# 32x35_V0_6.net
KiCad netlist of a schematic drawn in Altium Designer
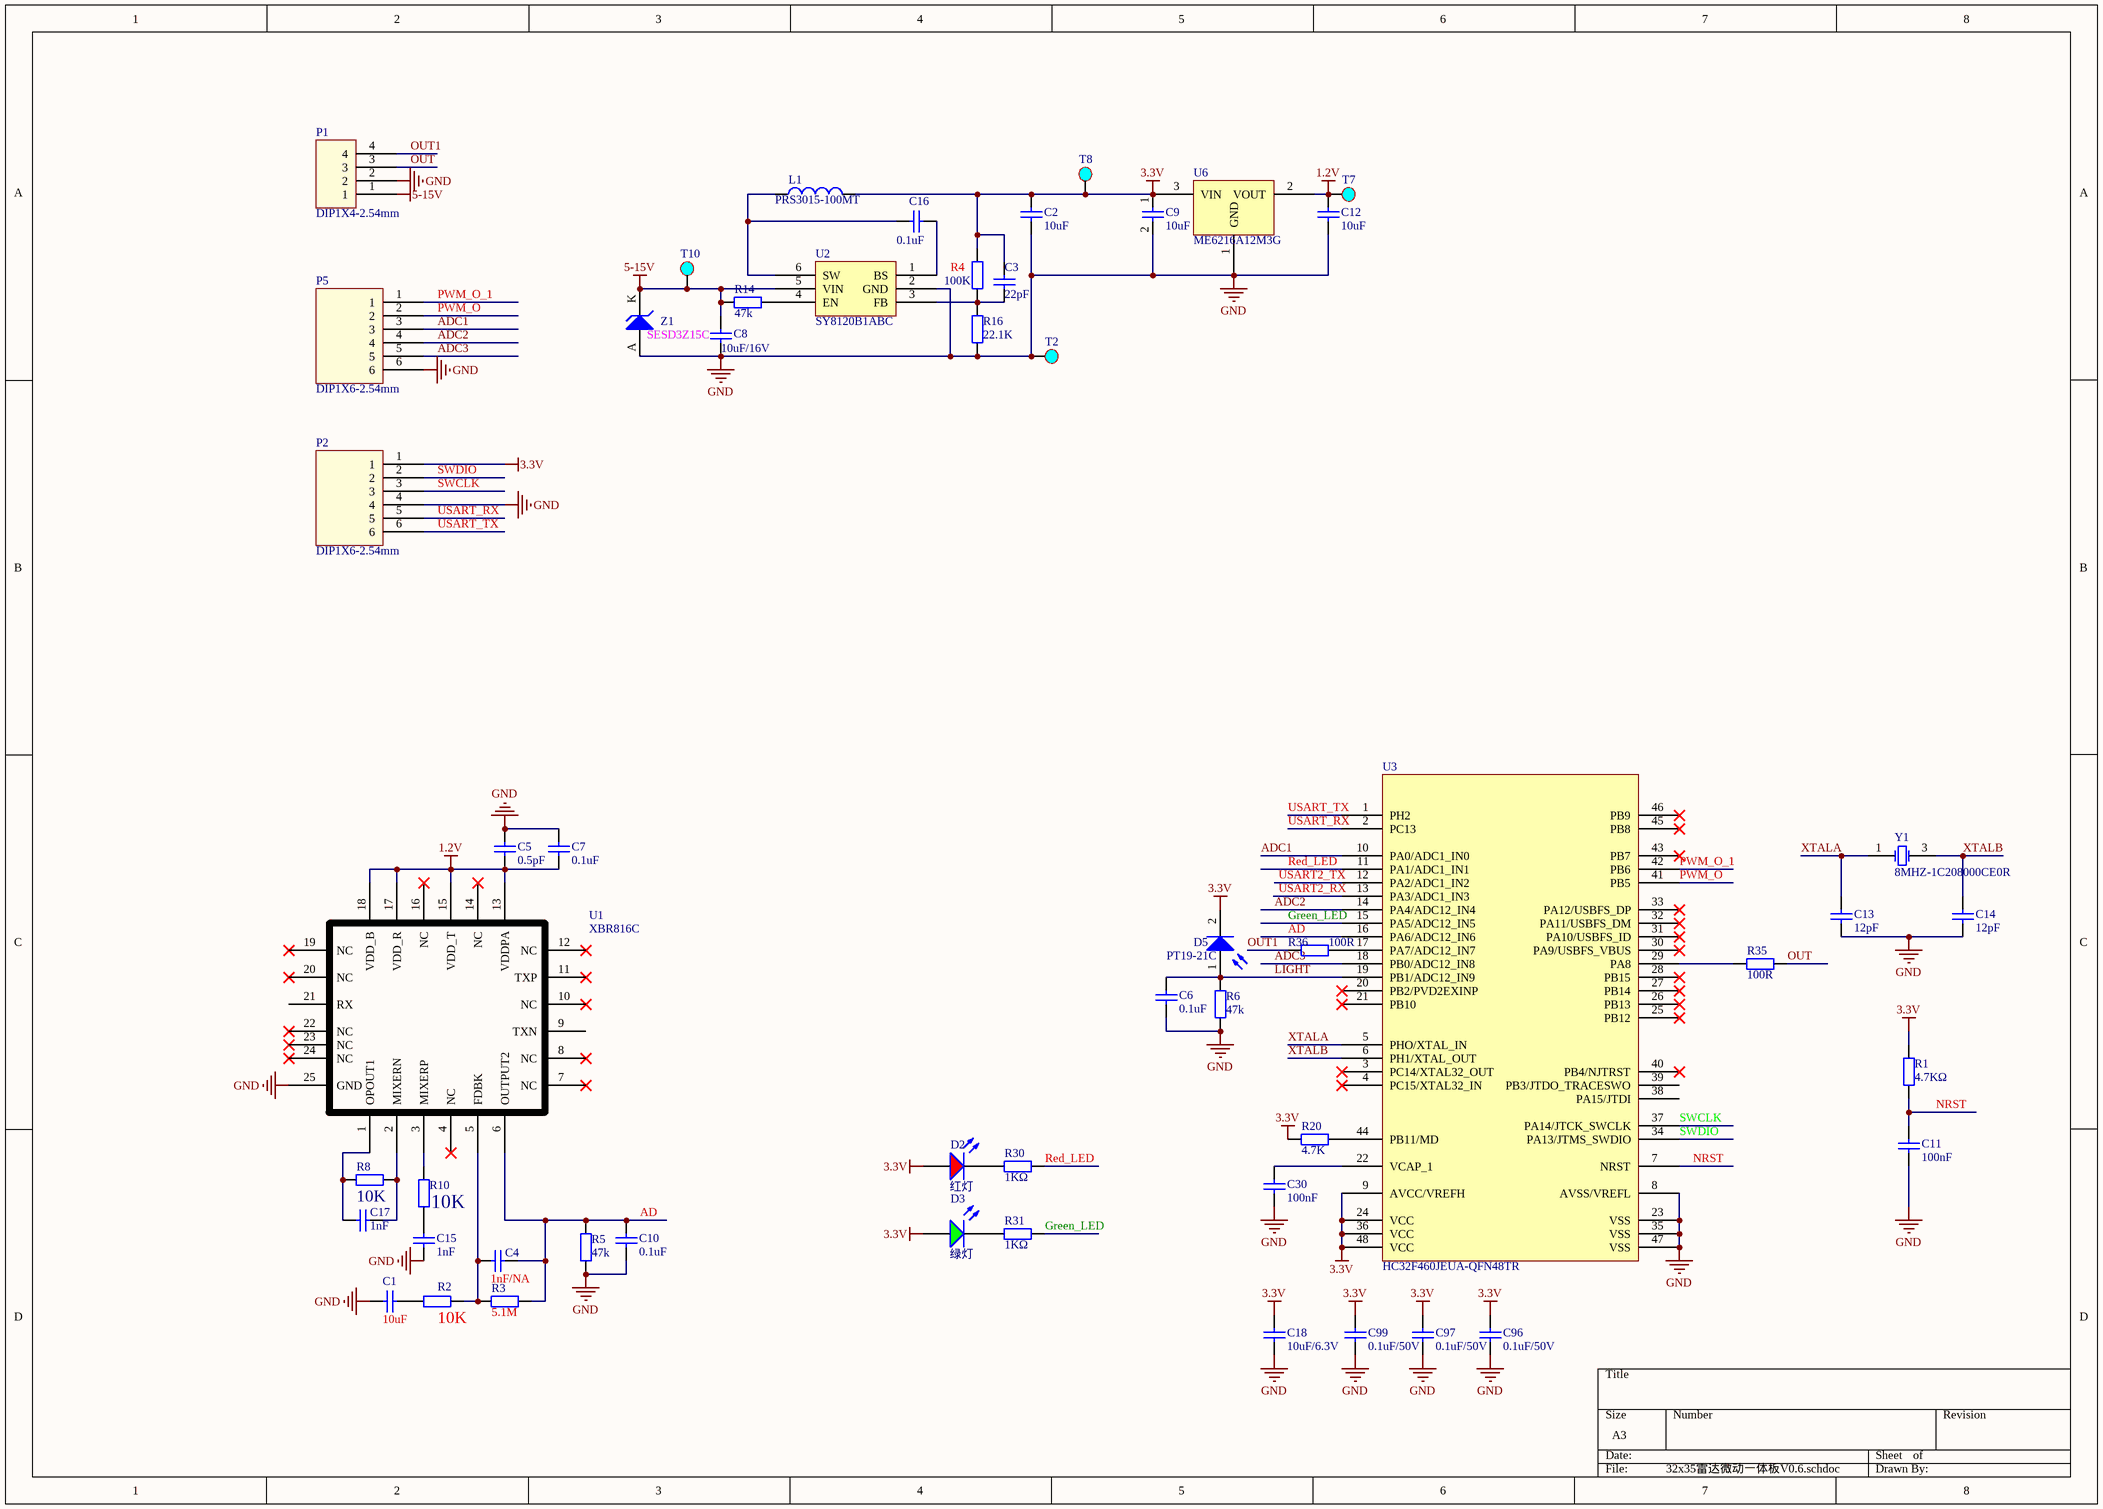
[diagram p0: 32x35雷达微动一体板V0.6.schdoc]

(export (version "E")
  (design (tool "Eeschema 10.0.6"))
  (components
    (comp (ref "C1")
      (value "10uF")
      (footprint "C0402")
      (description "Capacitor")
      (fields (field (name "PUBLISHER") "Altium Limited"))
      (libsource (lib "Miscellaneous Devices") (part "Cap"))
    )
    (comp (ref "C2")
      (value "10uF")
      (footprint "C0402")
      (description "Capacitor")
      (fields (field (name "PUBLISHER") "Altium Limited"))
      (libsource (lib "Miscellaneous Devices") (part "Cap"))
    )
    (comp (ref "C3")
      (value "22pF")
      (footprint "C0402")
      (description "Capacitor")
      (fields (field (name "PUBLISHER") "Altium Limited"))
      (libsource (lib "Miscellaneous Devices") (part "Cap"))
    )
    (comp (ref "C4")
      (value "1nF/NA")
      (footprint "C0402")
      (description "Capacitor")
      (fields (field (name "PUBLISHER") "Altium Limited"))
      (libsource (lib "Miscellaneous Devices") (part "Cap"))
    )
    (comp (ref "C5")
      (value "0.5pF")
      (footprint "C0402")
      (description "Capacitor")
      (fields (field (name "PUBLISHER") "Altium Limited"))
      (libsource (lib "Miscellaneous Devices") (part "Cap"))
    )
    (comp (ref "C6")
      (value "0.1uF")
      (footprint "C0402")
      (description "Capacitor")
      (fields (field (name "PUBLISHER") "Altium Limited"))
      (libsource (lib "Miscellaneous Devices") (part "Cap"))
    )
    (comp (ref "C7")
      (value "0.1uF")
      (footprint "C0402")
      (description "Capacitor")
      (fields (field (name "PUBLISHER") "Altium Limited"))
      (libsource (lib "Miscellaneous Devices") (part "Cap"))
    )
    (comp (ref "C8")
      (value "10uF/16V")
      (footprint "C0603")
      (description "Capacitor")
      (fields (field (name "PUBLISHER") "Altium Limited"))
      (libsource (lib "Miscellaneous Devices") (part "Cap"))
    )
    (comp (ref "C9")
      (value "10uF")
      (footprint "C0402")
      (description "Capacitor")
      (fields (field (name "PUBLISHER") "Altium Limited"))
      (libsource (lib "") (part "Cap_1"))
    )
    (comp (ref "C10")
      (value "0.1uF")
      (footprint "C0402")
      (description "Capacitor")
      (fields (field (name "PUBLISHER") "Altium Limited"))
      (libsource (lib "Miscellaneous Devices") (part "Cap"))
    )
    (comp (ref "C11")
      (value "100nF")
      (footprint "C0402")
      (description "贴片电容")
      (libsource (lib "Miscellaneous Devices LC") (part "0402 100nF (104) 10% 16V"))
    )
    (comp (ref "C12")
      (value "10uF")
      (footprint "C0402")
      (description "Capacitor")
      (fields (field (name "PUBLISHER") "Altium Limited"))
      (libsource (lib "Miscellaneous Devices") (part "Cap"))
    )
    (comp (ref "C13")
      (value "12pF")
      (footprint "C0402")
      (description "贴片电容")
      (libsource (lib "Cap") (part "0402 22pF (220) 5% 50V"))
    )
    (comp (ref "C14")
      (value "12pF")
      (footprint "C0402")
      (description "贴片电容")
      (libsource (lib "Cap") (part "0402 22pF (220) 5% 50V"))
    )
    (comp (ref "C15")
      (value "1nF")
      (footprint "C0402")
      (description "Capacitor")
      (fields (field (name "PUBLISHER") "Altium Limited"))
      (libsource (lib "Miscellaneous Devices") (part "Cap"))
    )
    (comp (ref "C16")
      (value "0.1uF")
      (footprint "C0402")
      (description "Capacitor")
      (fields (field (name "PUBLISHER") "Altium Limited"))
      (libsource (lib "Miscellaneous Devices") (part "Cap"))
    )
    (comp (ref "C17")
      (value "1nF")
      (footprint "C0402")
      (description "Capacitor")
      (fields (field (name "PUBLISHER") "Altium Limited"))
      (libsource (lib "Miscellaneous Devices") (part "Cap"))
    )
    (comp (ref "C18")
      (value "10uF/6.3V")
      (footprint "C0402")
      (description "贴片电容")
      (libsource (lib "Cap") (part "0402 2.2nF (222) 10% 50V"))
    )
    (comp (ref "C30")
      (value "100nF")
      (footprint "C0402")
      (description "Capacitor")
      (fields (field (name "PUBLISHER") "Altium Limited"))
      (libsource (lib "Miscellaneous Devices") (part "Cap"))
    )
    (comp (ref "C96")
      (value "0.1uF/50V")
      (footprint "C0402")
      (description "贴片电容")
      (libsource (lib "Cap") (part "0402 2.2nF (222) 10% 50V"))
    )
    (comp (ref "C97")
      (value "0.1uF/50V")
      (footprint "C0402")
      (description "贴片电容")
      (libsource (lib "Cap") (part "0402 2.2nF (222) 10% 50V"))
    )
    (comp (ref "C99")
      (value "0.1uF/50V")
      (footprint "C0402")
      (description "贴片电容")
      (libsource (lib "Cap") (part "0402 2.2nF (222) 10% 50V"))
    )
    (comp (ref "D2")
      (value "红灯")
      (footprint "LC-0603_LED_S1")
      (description "发光二极管")
      (libsource (lib "Miscellaneous Devices LC") (part "0603 红灯"))
    )
    (comp (ref "D3")
      (value "绿灯")
      (footprint "LC-0603_LED_S1")
      (description "发光二极管")
      (libsource (lib "30x35雷达微动底板V0.2") (part "0603 红灯"))
    )
    (comp (ref "D5")
      (value "PT19-21C")
      (footprint "LED-0603")
      (description "Photosensitive Diode")
      (fields (field (name "PUBLISHER") "Altium Limited"))
      (libsource (lib "Miscellaneous Devices") (part "Photo Sen"))
    )
    (comp (ref "L1")
      (value "PRS3015-100MT")
      (footprint "PRS3015")
      (description "Inductor")
      (fields (field (name "PUBLISHER") "Altium Limited"))
      (libsource (lib "Miscellaneous Devices") (part "Inductor"))
    )
    (comp (ref "P1")
      (value "DIP1X4-2.54mm")
      (footprint "DIP1X4-2.54mm")
      (libsource (lib "30x35雷达微动底板V0.2") (part "DIP4-2.54mm"))
    )
    (comp (ref "P2")
      (value "DIP1X6-2.54mm")
      (footprint "DIP1X6-2.54")
      (libsource (lib "30x35雷达微动底板V0.2") (part "DIP1X6-2.54mm"))
    )
    (comp (ref "P5")
      (value "DIP1X6-2.54mm")
      (footprint "DIP1X6-2.54")
      (libsource (lib "30x35雷达微动底板V0.2") (part "DIP1X6-2.54mm"))
    )
    (comp (ref "R1")
      (value "4.7KΩ")
      (footprint "R0402")
      (description "贴片电阻")
      (libsource (lib "") (part "0402 4.7KΩ (4701) 1%_1"))
    )
    (comp (ref "R2")
      (value "10K")
      (footprint "R0402")
      (description "Resistor")
      (fields (field (name "PUBLISHER") "Altium Limited"))
      (libsource (lib "") (part "Res2_1"))
    )
    (comp (ref "R3")
      (value "5.1M")
      (footprint "R0402")
      (description "Resistor")
      (fields (field (name "PUBLISHER") "Altium Limited"))
      (libsource (lib "Miscellaneous Devices") (part "Res2"))
    )
    (comp (ref "R4")
      (value "100K")
      (footprint "R0402")
      (description "Resistor")
      (fields (field (name "PUBLISHER") "Altium Limited"))
      (libsource (lib "") (part "Res2_3"))
    )
    (comp (ref "R5")
      (value "47k")
      (footprint "R0402")
      (description "Resistor")
      (fields (field (name "PUBLISHER") "Altium Limited"))
      (libsource (lib "") (part "Res2_2"))
    )
    (comp (ref "R6")
      (value "47k")
      (footprint "R0402")
      (description "Resistor")
      (fields (field (name "PUBLISHER") "Altium Limited"))
      (libsource (lib "") (part "Res2_2"))
    )
    (comp (ref "R8")
      (value "10K")
      (footprint "R0402")
      (description "Resistor")
      (fields (field (name "PUBLISHER") "Altium Limited"))
      (libsource (lib "Miscellaneous Devices") (part "Res2"))
    )
    (comp (ref "R10")
      (value "10K")
      (footprint "R0402")
      (description "Resistor")
      (fields (field (name "PUBLISHER") "Altium Limited"))
      (libsource (lib "") (part "Res2_2"))
    )
    (comp (ref "R14")
      (value "47k")
      (footprint "R0402")
      (description "Resistor")
      (fields (field (name "PUBLISHER") "Altium Limited"))
      (libsource (lib "Miscellaneous Devices") (part "Res2"))
    )
    (comp (ref "R16")
      (value "22.1K")
      (footprint "R0402")
      (description "Resistor")
      (fields (field (name "PUBLISHER") "Altium Limited"))
      (libsource (lib "") (part "Res2_3"))
    )
    (comp (ref "R20")
      (value "4.7K")
      (footprint "R0402")
      (description "Resistor")
      (fields (field (name "PUBLISHER") "Altium Limited"))
      (libsource (lib "") (part "Res2_1"))
    )
    (comp (ref "R30")
      (value "1KΩ")
      (footprint "R0402")
      (description "贴片电阻")
      (libsource (lib "Miscellaneous Devices LC") (part "0402 1KΩ (1001) 1%"))
    )
    (comp (ref "R31")
      (value "1KΩ")
      (footprint "R0402")
      (description "贴片电阻")
      (libsource (lib "Miscellaneous Devices LC") (part "0402 1KΩ (1001) 1%"))
    )
    (comp (ref "R35")
      (value "100R")
      (footprint "R0402")
      (description "贴片电阻")
      (libsource (lib "Miscellaneous Devices LC") (part "0402 4.7KΩ (4701) 1%"))
    )
    (comp (ref "R36")
      (value "100R")
      (footprint "R0402")
      (description "贴片电阻")
      (libsource (lib "Miscellaneous Devices LC") (part "0402 4.7KΩ (4701) 1%"))
    )
    (comp (ref "T2")
      (value "~")
      (footprint "TestPoints")
      (description "TestPoints")
      (libsource (lib "标准原理图库（特种板）") (part "TestPoints"))
    )
    (comp (ref "T7")
      (value "~")
      (footprint "TestPoints")
      (description "TestPoints")
      (libsource (lib "标准原理图库（特种板）") (part "TestPoints"))
    )
    (comp (ref "T8")
      (value "~")
      (footprint "TestPoints")
      (description "TestPoints")
      (libsource (lib "标准原理图库（特种板）") (part "TestPoints"))
    )
    (comp (ref "T10")
      (value "~")
      (footprint "TestPoints")
      (description "TestPoints")
      (libsource (lib "标准原理图库（特种板）") (part "TestPoints"))
    )
    (comp (ref "U1")
      (value "XBR816C")
      (footprint "XBR816")
      (libsource (lib "HX-V0.1-20201202") (part "XBR1000_24_1"))
    )
    (comp (ref "U2") (value "SY8120B1ABC") (footprint "SOT-23-6") (libsource (lib "Schlib1") (part "H9108")))
    (comp (ref "U3")
      (value "HC32F460JEUA-QFN48TR")
      (footprint "QFN48-5X5mm")
      (libsource (lib "LD-ShouShi-Module-V1.0") (part "HC32F460JETA-LQFP48"))
    )
    (comp (ref "U6")
      (value "ME6216A12M3G")
      (footprint "SOT-23-L")
      (libsource (lib "Schlib1") (part "SSP6206"))
    )
    (comp (ref "Y1")
      (value "8MHZ-1C208000CE0R")
      (footprint "OSC-SMD_3225")
      (description "贴片晶振")
      (libsource (lib "CrystalOscillator") (part "SMD-3225_4P  25MHZ 12PF 10PPM"))
    )
    (comp (ref "Z1")
      (value "SESD3Z15C")
      (footprint "SOD323")
      (description "Zener Diode")
      (fields (field (name "PUBLISHER") "Altium Limited"))
      (libsource (lib "Miscellaneous Devices") (part "D Zener"))
    )
  )
  (nets
    (net (code "1") (name "/AD") (class "Default")
      (node (ref "C10") (pin "1") (pinfunction "1_1") (pintype "passive"))
      (node (ref "C4") (pin "1") (pinfunction "1_1") (pintype "passive"))
      (node (ref "R3") (pin "1") (pinfunction "1_1") (pintype "passive"))
      (node (ref "R5") (pin "1") (pinfunction "1_1") (pintype "passive"))
      (node (ref "U1") (pin "6") (pinfunction "OUTPUT2_6") (pintype "passive"))
      (node (ref "U3") (pin "16") (pinfunction "PA6/ADC12_IN6_16") (pintype "passive"))
    )
    (net (code "2") (name "/ADC1") (class "Default")
      (node (ref "P5") (pin "3") (pinfunction "3_3") (pintype "passive"))
      (node (ref "U3") (pin "10") (pinfunction "PA0/ADC1_IN0_10") (pintype "passive"))
    )
    (net (code "3") (name "/ADC2") (class "Default")
      (node (ref "P5") (pin "4") (pinfunction "4_4") (pintype "passive"))
      (node (ref "U3") (pin "14") (pinfunction "PA4/ADC12_IN4_14") (pintype "passive"))
    )
    (net (code "4") (name "/ADC3") (class "Default")
      (node (ref "P5") (pin "5") (pinfunction "5_5") (pintype "passive"))
      (node (ref "U3") (pin "18") (pinfunction "PB0/ADC12_IN8_18") (pintype "passive"))
    )
    (net (code "5") (name "/Green_LED") (class "Default")
      (node (ref "R31") (pin "1") (pinfunction "1_1") (pintype "passive"))
      (node (ref "U3") (pin "15") (pinfunction "PA5/ADC12_IN5_15") (pintype "passive"))
    )
    (net (code "6") (name "/LIGHT") (class "Default")
      (node (ref "C6") (pin "1") (pinfunction "1_1") (pintype "passive"))
      (node (ref "D5") (pin "1") (pinfunction "A_1") (pintype "passive"))
      (node (ref "R6") (pin "1") (pinfunction "1_1") (pintype "passive"))
      (node (ref "U3") (pin "19") (pinfunction "PB1/ADC12_IN9_19") (pintype "passive"))
    )
    (net (code "7") (name "/NRST") (class "Default")
      (node (ref "C11") (pin "2") (pinfunction "2_2") (pintype "passive"))
      (node (ref "R1") (pin "1") (pinfunction "1_1") (pintype "passive"))
      (node (ref "U3") (pin "7") (pinfunction "NRST_7") (pintype "passive"))
    )
    (net (code "8") (name "/OUT") (class "Default")
      (node (ref "P1") (pin "3") (pinfunction "3_3") (pintype "passive"))
      (node (ref "R35") (pin "1") (pinfunction "1_1") (pintype "passive"))
    )
    (net (code "9") (name "/OUT1") (class "Default")
      (node (ref "P1") (pin "4") (pinfunction "4_4") (pintype "passive"))
      (node (ref "R36") (pin "2") (pinfunction "2_2") (pintype "passive"))
    )
    (net (code "10") (name "/PWM_O") (class "Default")
      (node (ref "P5") (pin "2") (pinfunction "2_2") (pintype "passive"))
      (node (ref "U3") (pin "41") (pinfunction "PB5_41") (pintype "passive"))
    )
    (net (code "11") (name "/PWM_O_1") (class "Default")
      (node (ref "P5") (pin "1") (pinfunction "1_1") (pintype "passive"))
      (node (ref "U3") (pin "42") (pinfunction "PB6_42") (pintype "passive"))
    )
    (net (code "12") (name "/Red_LED") (class "Default")
      (node (ref "R30") (pin "1") (pinfunction "1_1") (pintype "passive"))
      (node (ref "U3") (pin "11") (pinfunction "PA1/ADC1_IN1_11") (pintype "passive"))
    )
    (net (code "13") (name "/SWCLK") (class "Default")
      (node (ref "P2") (pin "3") (pinfunction "3_3") (pintype "passive"))
      (node (ref "U3") (pin "37") (pinfunction "PA14/JTCK_SWCLK_37") (pintype "passive"))
    )
    (net (code "14") (name "/SWDIO") (class "Default")
      (node (ref "P2") (pin "2") (pinfunction "2_2") (pintype "passive"))
      (node (ref "U3") (pin "34") (pinfunction "PA13/JTMS_SWDIO_34") (pintype "passive"))
    )
    (net (code "15") (name "/USART2_RX") (class "Default")
      (node (ref "U3") (pin "13") (pinfunction "PA3/ADC1_IN3_13") (pintype "passive"))
    )
    (net (code "16") (name "/USART2_TX") (class "Default")
      (node (ref "U3") (pin "12") (pinfunction "PA2/ADC1_IN2_12") (pintype "passive"))
    )
    (net (code "17") (name "/USART_RX") (class "Default")
      (node (ref "P2") (pin "5") (pinfunction "5_5") (pintype "passive"))
      (node (ref "U3") (pin "2") (pinfunction "PC13_2") (pintype "passive"))
    )
    (net (code "18") (name "/USART_TX") (class "Default")
      (node (ref "P2") (pin "6") (pinfunction "6_6") (pintype "passive"))
      (node (ref "U3") (pin "1") (pinfunction "PH2_1") (pintype "passive"))
    )
    (net (code "19") (name "/XTALA") (class "Default")
      (node (ref "C13") (pin "2") (pinfunction "2_2") (pintype "passive"))
      (node (ref "U3") (pin "5") (pinfunction "PHO/XTAL_IN_5") (pintype "passive"))
      (node (ref "Y1") (pin "1") (pinfunction "OSC1_1") (pintype "passive"))
    )
    (net (code "20") (name "/XTALB") (class "Default")
      (node (ref "C14") (pin "2") (pinfunction "2_2") (pintype "passive"))
      (node (ref "U3") (pin "6") (pinfunction "PH1/XTAL_OUT_6") (pintype "passive"))
      (node (ref "Y1") (pin "3") (pinfunction "OSC2_3") (pintype "passive"))
    )
    (net (code "21") (name "1.2V") (class "Default")
      (node (ref "C12") (pin "1") (pinfunction "1_1") (pintype "passive"))
      (node (ref "C5") (pin "1") (pinfunction "1_1") (pintype "passive"))
      (node (ref "C7") (pin "1") (pinfunction "1_1") (pintype "passive"))
      (node (ref "T7") (pin "1") (pinfunction "1_1") (pintype "passive"))
      (node (ref "U1") (pin "13") (pinfunction "VDDPA_13") (pintype "passive"))
      (node (ref "U1") (pin "15") (pinfunction "VDD_T_15") (pintype "passive"))
      (node (ref "U1") (pin "17") (pinfunction "VDD_R_17") (pintype "passive"))
      (node (ref "U1") (pin "18") (pinfunction "VDD_B_18") (pintype "passive"))
      (node (ref "U6") (pin "2") (pinfunction "VOUT_2") (pintype "passive"))
    )
    (net (code "22") (name "3.3V") (class "Default")
      (node (ref "C18") (pin "1") (pinfunction "1_1") (pintype "passive"))
      (node (ref "C2") (pin "1") (pinfunction "1_1") (pintype "passive"))
      (node (ref "C3") (pin "2") (pinfunction "2_2") (pintype "passive"))
      (node (ref "C9") (pin "1") (pinfunction "1_1") (pintype "passive"))
      (node (ref "C96") (pin "1") (pinfunction "1_1") (pintype "passive"))
      (node (ref "C97") (pin "1") (pinfunction "1_1") (pintype "passive"))
      (node (ref "C99") (pin "1") (pinfunction "1_1") (pintype "passive"))
      (node (ref "D2") (pin "A") (pinfunction "A_A") (pintype "passive"))
      (node (ref "D3") (pin "A") (pinfunction "A_A") (pintype "passive"))
      (node (ref "D5") (pin "2") (pinfunction "K_2") (pintype "passive"))
      (node (ref "L1") (pin "2") (pinfunction "2_2") (pintype "passive"))
      (node (ref "P2") (pin "1") (pinfunction "1_1") (pintype "passive"))
      (node (ref "R1") (pin "2") (pinfunction "2_2") (pintype "passive"))
      (node (ref "R20") (pin "1") (pinfunction "1_1") (pintype "passive"))
      (node (ref "R4") (pin "2") (pinfunction "2_2") (pintype "passive"))
      (node (ref "T8") (pin "1") (pinfunction "1_1") (pintype "passive"))
      (node (ref "U3") (pin "24") (pinfunction "VCC_24") (pintype "passive"))
      (node (ref "U3") (pin "36") (pinfunction "VCC_36") (pintype "passive"))
      (node (ref "U3") (pin "48") (pinfunction "VCC_48") (pintype "passive"))
      (node (ref "U3") (pin "9") (pinfunction "AVCC/VREFH_9") (pintype "passive"))
      (node (ref "U6") (pin "3") (pinfunction "VIN_3") (pintype "passive"))
    )
    (net (code "23") (name "5-15V") (class "Default")
      (node (ref "C8") (pin "1") (pinfunction "1_1") (pintype "passive"))
      (node (ref "P1") (pin "1") (pinfunction "1_1") (pintype "passive"))
      (node (ref "R14") (pin "2") (pinfunction "2_2") (pintype "passive"))
      (node (ref "T10") (pin "1") (pinfunction "1_1") (pintype "passive"))
      (node (ref "U2") (pin "5") (pinfunction "VIN_5") (pintype "passive"))
      (node (ref "Z1") (pin "K") (pinfunction "K_K") (pintype "passive"))
    )
    (net (code "24") (name "GND") (class "Default")
      (node (ref "C1") (pin "2") (pinfunction "2_2") (pintype "passive"))
      (node (ref "C10") (pin "2") (pinfunction "2_2") (pintype "passive"))
      (node (ref "C11") (pin "1") (pinfunction "1_1") (pintype "passive"))
      (node (ref "C12") (pin "2") (pinfunction "2_2") (pintype "passive"))
      (node (ref "C13") (pin "1") (pinfunction "1_1") (pintype "passive"))
      (node (ref "C14") (pin "1") (pinfunction "1_1") (pintype "passive"))
      (node (ref "C15") (pin "1") (pinfunction "1_1") (pintype "passive"))
      (node (ref "C18") (pin "2") (pinfunction "2_2") (pintype "passive"))
      (node (ref "C2") (pin "2") (pinfunction "2_2") (pintype "passive"))
      (node (ref "C30") (pin "2") (pinfunction "2_2") (pintype "passive"))
      (node (ref "C5") (pin "2") (pinfunction "2_2") (pintype "passive"))
      (node (ref "C6") (pin "2") (pinfunction "2_2") (pintype "passive"))
      (node (ref "C7") (pin "2") (pinfunction "2_2") (pintype "passive"))
      (node (ref "C8") (pin "2") (pinfunction "2_2") (pintype "passive"))
      (node (ref "C9") (pin "2") (pinfunction "2_2") (pintype "passive"))
      (node (ref "C96") (pin "2") (pinfunction "2_2") (pintype "passive"))
      (node (ref "C97") (pin "2") (pinfunction "2_2") (pintype "passive"))
      (node (ref "C99") (pin "2") (pinfunction "2_2") (pintype "passive"))
      (node (ref "P1") (pin "2") (pinfunction "2_2") (pintype "passive"))
      (node (ref "P2") (pin "4") (pinfunction "4_4") (pintype "passive"))
      (node (ref "P5") (pin "6") (pinfunction "6_6") (pintype "passive"))
      (node (ref "R16") (pin "1") (pinfunction "1_1") (pintype "passive"))
      (node (ref "R5") (pin "2") (pinfunction "2_2") (pintype "passive"))
      (node (ref "R6") (pin "2") (pinfunction "2_2") (pintype "passive"))
      (node (ref "T2") (pin "1") (pinfunction "1_1") (pintype "passive"))
      (node (ref "U1") (pin "25") (pinfunction "GND_25") (pintype "passive"))
      (node (ref "U2") (pin "2") (pinfunction "GND_2") (pintype "passive"))
      (node (ref "U3") (pin "23") (pinfunction "VSS_23") (pintype "passive"))
      (node (ref "U3") (pin "35") (pinfunction "VSS_35") (pintype "passive"))
      (node (ref "U3") (pin "47") (pinfunction "VSS_47") (pintype "passive"))
      (node (ref "U3") (pin "8") (pinfunction "AVSS/VREFL_8") (pintype "passive"))
      (node (ref "U6") (pin "1") (pinfunction "GND_1") (pintype "passive"))
      (node (ref "Z1") (pin "A") (pinfunction "A_A") (pintype "passive"))
    )
    (net (code "25") (name "Net-(C1-Pad1)") (class "Default")
      (node (ref "C1") (pin "1") (pinfunction "1_1") (pintype "passive"))
      (node (ref "R2") (pin "1") (pinfunction "1_1") (pintype "passive"))
    )
    (net (code "26") (name "Net-(C15-Pad2)") (class "Default")
      (node (ref "C15") (pin "2") (pinfunction "2_2") (pintype "passive"))
      (node (ref "R10") (pin "2") (pinfunction "2_2") (pintype "passive"))
    )
    (net (code "27") (name "Net-(D2-PadK)") (class "Default")
      (node (ref "D2") (pin "K") (pinfunction "K_K") (pintype "passive"))
      (node (ref "R30") (pin "2") (pinfunction "2_2") (pintype "passive"))
    )
    (net (code "28") (name "Net-(D3-PadK)") (class "Default")
      (node (ref "D3") (pin "K") (pinfunction "K_K") (pintype "passive"))
      (node (ref "R31") (pin "2") (pinfunction "2_2") (pintype "passive"))
    )
    (net (code "29") (name "Net-(U1-FDBK)") (class "Default")
      (node (ref "C4") (pin "2") (pinfunction "2_2") (pintype "passive"))
      (node (ref "R2") (pin "2") (pinfunction "2_2") (pintype "passive"))
      (node (ref "R3") (pin "2") (pinfunction "2_2") (pintype "passive"))
      (node (ref "U1") (pin "5") (pinfunction "FDBK_5") (pintype "passive"))
    )
    (net (code "30") (name "Net-(U1-MIXERN)") (class "Default")
      (node (ref "C17") (pin "1") (pinfunction "1_1") (pintype "passive"))
      (node (ref "R8") (pin "1") (pinfunction "1_1") (pintype "passive"))
      (node (ref "U1") (pin "2") (pinfunction "MIXERN_2") (pintype "passive"))
    )
    (net (code "31") (name "Net-(U1-MIXERP)") (class "Default")
      (node (ref "R10") (pin "1") (pinfunction "1_1") (pintype "passive"))
      (node (ref "U1") (pin "3") (pinfunction "MIXERP_3") (pintype "passive"))
    )
    (net (code "32") (name "Net-(U1-OPOUT1)") (class "Default")
      (node (ref "C17") (pin "2") (pinfunction "2_2") (pintype "passive"))
      (node (ref "R8") (pin "2") (pinfunction "2_2") (pintype "passive"))
      (node (ref "U1") (pin "1") (pinfunction "OPOUT1_1") (pintype "passive"))
    )
    (net (code "33") (name "Net-(U2-BS)") (class "Default")
      (node (ref "C16") (pin "2") (pinfunction "2_2") (pintype "passive"))
      (node (ref "U2") (pin "1") (pinfunction "BS_1") (pintype "passive"))
    )
    (net (code "34") (name "Net-(U2-EN)") (class "Default")
      (node (ref "R14") (pin "1") (pinfunction "1_1") (pintype "passive"))
      (node (ref "U2") (pin "4") (pinfunction "EN_4") (pintype "passive"))
    )
    (net (code "35") (name "Net-(U2-FB)") (class "Default")
      (node (ref "C3") (pin "1") (pinfunction "1_1") (pintype "passive"))
      (node (ref "R16") (pin "2") (pinfunction "2_2") (pintype "passive"))
      (node (ref "R4") (pin "1") (pinfunction "1_1") (pintype "passive"))
      (node (ref "U2") (pin "3") (pinfunction "FB_3") (pintype "passive"))
    )
    (net (code "36") (name "Net-(U2-SW)") (class "Default")
      (node (ref "C16") (pin "1") (pinfunction "1_1") (pintype "passive"))
      (node (ref "L1") (pin "1") (pinfunction "1_1") (pintype "passive"))
      (node (ref "U2") (pin "6") (pinfunction "SW_6") (pintype "passive"))
    )
    (net (code "37") (name "Net-(U3-PA7{slash}ADC12_IN7)") (class "Default")
      (node (ref "R36") (pin "1") (pinfunction "1_1") (pintype "passive"))
      (node (ref "U3") (pin "17") (pinfunction "PA7/ADC12_IN7_17") (pintype "passive"))
    )
    (net (code "38") (name "Net-(U3-PA8)") (class "Default")
      (node (ref "R35") (pin "2") (pinfunction "2_2") (pintype "passive"))
      (node (ref "U3") (pin "29") (pinfunction "PA8_29") (pintype "passive"))
    )
    (net (code "39") (name "Net-(U3-PB11{slash}MD)") (class "Default")
      (node (ref "R20") (pin "2") (pinfunction "2_2") (pintype "passive"))
      (node (ref "U3") (pin "44") (pinfunction "PB11/MD_44") (pintype "passive"))
    )
    (net (code "40") (name "Net-(U3-VCAP_1)") (class "Default")
      (node (ref "C30") (pin "1") (pinfunction "1_1") (pintype "passive"))
      (node (ref "U3") (pin "22") (pinfunction "VCAP_1_22") (pintype "passive"))
    )
    (net (code "41") (name "unconnected-(U1-NC-Pad4)") (class "Default")
      (node (ref "U1") (pin "4") (pinfunction "NC_4") (pintype "passive+no_connect"))
    )
    (net (code "42") (name "unconnected-(U1-NC-Pad7)") (class "Default")
      (node (ref "U1") (pin "7") (pinfunction "NC_7") (pintype "passive+no_connect"))
    )
    (net (code "43") (name "unconnected-(U1-NC-Pad8)") (class "Default")
      (node (ref "U1") (pin "8") (pinfunction "NC_8") (pintype "passive+no_connect"))
    )
    (net (code "44") (name "unconnected-(U1-NC-Pad10)") (class "Default")
      (node (ref "U1") (pin "10") (pinfunction "NC_10") (pintype "passive+no_connect"))
    )
    (net (code "45") (name "unconnected-(U1-NC-Pad12)") (class "Default")
      (node (ref "U1") (pin "12") (pinfunction "NC_12") (pintype "passive+no_connect"))
    )
    (net (code "46") (name "unconnected-(U1-NC-Pad14)") (class "Default")
      (node (ref "U1") (pin "14") (pinfunction "NC_14") (pintype "passive+no_connect"))
    )
    (net (code "47") (name "unconnected-(U1-NC-Pad16)") (class "Default")
      (node (ref "U1") (pin "16") (pinfunction "NC_16") (pintype "passive+no_connect"))
    )
    (net (code "48") (name "unconnected-(U1-NC-Pad19)") (class "Default")
      (node (ref "U1") (pin "19") (pinfunction "NC_19") (pintype "passive+no_connect"))
    )
    (net (code "49") (name "unconnected-(U1-NC-Pad20)") (class "Default")
      (node (ref "U1") (pin "20") (pinfunction "NC_20") (pintype "passive+no_connect"))
    )
    (net (code "50") (name "unconnected-(U1-NC-Pad22)") (class "Default")
      (node (ref "U1") (pin "22") (pinfunction "NC_22") (pintype "passive+no_connect"))
    )
    (net (code "51") (name "unconnected-(U1-NC-Pad23)") (class "Default")
      (node (ref "U1") (pin "23") (pinfunction "NC_23") (pintype "passive+no_connect"))
    )
    (net (code "52") (name "unconnected-(U1-NC-Pad24)") (class "Default")
      (node (ref "U1") (pin "24") (pinfunction "NC_24") (pintype "passive+no_connect"))
    )
    (net (code "53") (name "unconnected-(U1-RX-Pad21)") (class "Default")
      (node (ref "U1") (pin "21") (pinfunction "RX_21") (pintype "passive"))
    )
    (net (code "54") (name "unconnected-(U1-TXN-Pad9)") (class "Default")
      (node (ref "U1") (pin "9") (pinfunction "TXN_9") (pintype "passive"))
    )
    (net (code "55") (name "unconnected-(U1-TXP-Pad11)") (class "Default")
      (node (ref "U1") (pin "11") (pinfunction "TXP_11") (pintype "passive+no_connect"))
    )
    (net (code "56") (name "unconnected-(U3-PA9{slash}USBFS_VBUS-Pad30)") (class "Default")
      (node (ref "U3") (pin "30") (pinfunction "PA9/USBFS_VBUS_30") (pintype "passive+no_connect"))
    )
    (net (code "57") (name "unconnected-(U3-PA10{slash}USBFS_ID-Pad31)") (class "Default")
      (node (ref "U3") (pin "31") (pinfunction "PA10/USBFS_ID_31") (pintype "passive+no_connect"))
    )
    (net (code "58") (name "unconnected-(U3-PA11{slash}USBFS_DM-Pad32)") (class "Default")
      (node (ref "U3") (pin "32") (pinfunction "PA11/USBFS_DM_32") (pintype "passive+no_connect"))
    )
    (net (code "59") (name "unconnected-(U3-PA12{slash}USBFS_DP-Pad33)") (class "Default")
      (node (ref "U3") (pin "33") (pinfunction "PA12/USBFS_DP_33") (pintype "passive+no_connect"))
    )
    (net (code "60") (name "unconnected-(U3-PA15{slash}JTDI-Pad38)") (class "Default")
      (node (ref "U3") (pin "38") (pinfunction "PA15/JTDI_38") (pintype "passive"))
    )
    (net (code "61") (name "unconnected-(U3-PB2{slash}PVD2EXINP-Pad20)") (class "Default")
      (node (ref "U3") (pin "20") (pinfunction "PB2/PVD2EXINP_20") (pintype "passive+no_connect"))
    )
    (net (code "62") (name "unconnected-(U3-PB3{slash}JTDO_TRACESWO-Pad39)") (class "Default")
      (node (ref "U3") (pin "39") (pinfunction "PB3/JTDO_TRACESWO_39") (pintype "passive"))
    )
    (net (code "63") (name "unconnected-(U3-PB4{slash}NJTRST-Pad40)") (class "Default")
      (node (ref "U3") (pin "40") (pinfunction "PB4/NJTRST_40") (pintype "passive+no_connect"))
    )
    (net (code "64") (name "unconnected-(U3-PB7-Pad43)") (class "Default")
      (node (ref "U3") (pin "43") (pinfunction "PB7_43") (pintype "passive+no_connect"))
    )
    (net (code "65") (name "unconnected-(U3-PB8-Pad45)") (class "Default")
      (node (ref "U3") (pin "45") (pinfunction "PB8_45") (pintype "passive+no_connect"))
    )
    (net (code "66") (name "unconnected-(U3-PB9-Pad46)") (class "Default")
      (node (ref "U3") (pin "46") (pinfunction "PB9_46") (pintype "passive+no_connect"))
    )
    (net (code "67") (name "unconnected-(U3-PB10-Pad21)") (class "Default")
      (node (ref "U3") (pin "21") (pinfunction "PB10_21") (pintype "passive+no_connect"))
    )
    (net (code "68") (name "unconnected-(U3-PB12-Pad25)") (class "Default")
      (node (ref "U3") (pin "25") (pinfunction "PB12_25") (pintype "passive+no_connect"))
    )
    (net (code "69") (name "unconnected-(U3-PB13-Pad26)") (class "Default")
      (node (ref "U3") (pin "26") (pinfunction "PB13_26") (pintype "passive+no_connect"))
    )
    (net (code "70") (name "unconnected-(U3-PB14-Pad27)") (class "Default")
      (node (ref "U3") (pin "27") (pinfunction "PB14_27") (pintype "passive+no_connect"))
    )
    (net (code "71") (name "unconnected-(U3-PB15-Pad28)") (class "Default")
      (node (ref "U3") (pin "28") (pinfunction "PB15_28") (pintype "passive+no_connect"))
    )
    (net (code "72") (name "unconnected-(U3-PC14{slash}XTAL32_OUT-Pad3)") (class "Default")
      (node (ref "U3") (pin "3") (pinfunction "PC14/XTAL32_OUT_3") (pintype "passive+no_connect"))
    )
    (net (code "73") (name "unconnected-(U3-PC15{slash}XTAL32_IN-Pad4)") (class "Default")
      (node (ref "U3") (pin "4") (pinfunction "PC15/XTAL32_IN_4") (pintype "passive+no_connect"))
    )
  )
)
